# 5-1_fgpa_power.net
KiCad netlist of a schematic drawn in Altium Designer
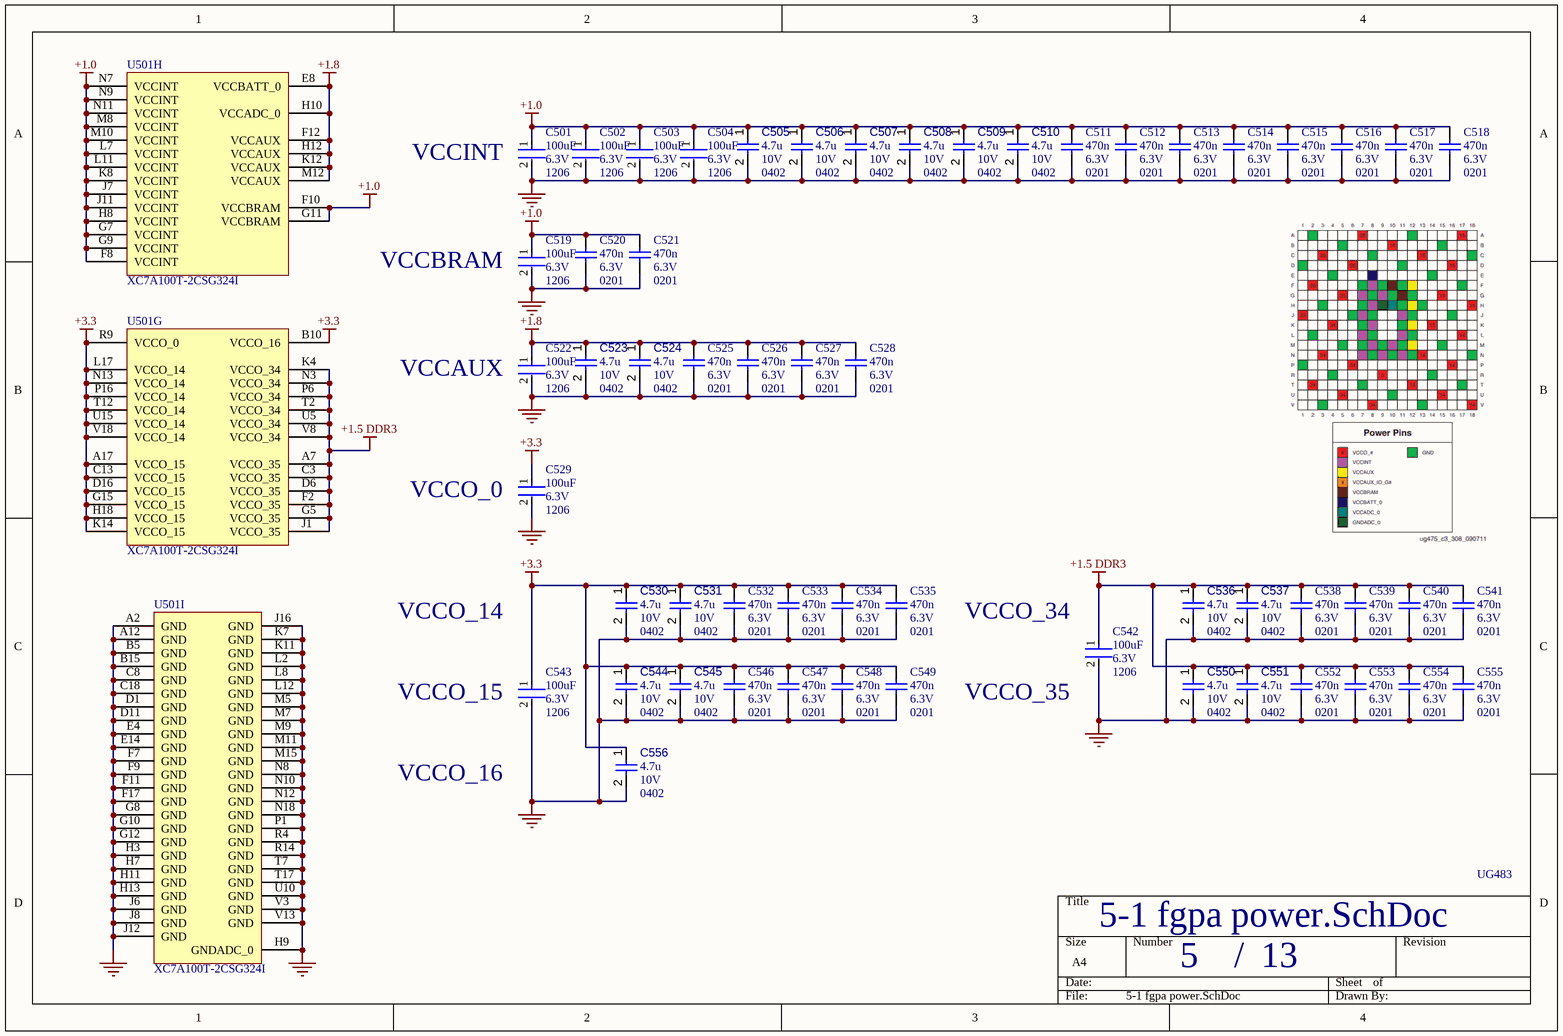
[diagram p0: 5-1 fgpa power.SchDoc]

(export (version "E")
  (design (tool "Eeschema 10.0.6"))
  (components
    (comp (ref "C501")
      (value "C1206C107M9PACTU")
      (footprint "FP-C1206C-EH-MFG")
      (description "CAP CER 100UF 6.3V X5R 1206")
      (fields
        (field (name "CASE CODE (IMPERIAL)") "1206")
        (field (name "VOLTAGE RATING (DC)") "6.3V")
        (field (name "TOLERANCE") "2%")
        (field (name "CAPACITANCE") "100uF")
        (field (name "VOLTAGE") "6.3V")
      )
      (libsource (lib "Altium Content Vault") (part "02cd4be3c70576c341d710602a673aa"))
    )
    (comp (ref "C502")
      (value "C1206C107M9PACTU")
      (footprint "FP-C1206C-EH-MFG")
      (description "CAP CER 100UF 6.3V X5R 1206")
      (fields
        (field (name "CASE CODE (IMPERIAL)") "1206")
        (field (name "VOLTAGE RATING (DC)") "6.3V")
        (field (name "TOLERANCE") "2%")
        (field (name "CAPACITANCE") "100uF")
        (field (name "VOLTAGE") "6.3V")
      )
      (libsource (lib "Altium Content Vault") (part "02cd4be3c70576c341d710602a673aa"))
    )
    (comp (ref "C503")
      (value "C1206C107M9PACTU")
      (footprint "FP-C1206C-EH-MFG")
      (description "CAP CER 100UF 6.3V X5R 1206")
      (fields
        (field (name "CASE CODE (IMPERIAL)") "1206")
        (field (name "VOLTAGE RATING (DC)") "6.3V")
        (field (name "TOLERANCE") "2%")
        (field (name "CAPACITANCE") "100uF")
        (field (name "VOLTAGE") "6.3V")
      )
      (libsource (lib "Altium Content Vault") (part "02cd4be3c70576c341d710602a673aa"))
    )
    (comp (ref "C504")
      (value "C1206C107M9PACTU")
      (footprint "FP-C1206C-EH-MFG")
      (description "CAP CER 100UF 6.3V X5R 1206")
      (fields
        (field (name "CASE CODE (IMPERIAL)") "1206")
        (field (name "VOLTAGE RATING (DC)") "6.3V")
        (field (name "TOLERANCE") "2%")
        (field (name "CAPACITANCE") "100uF")
        (field (name "VOLTAGE") "6.3V")
      )
      (libsource (lib "Altium Content Vault") (part "02cd4be3c70576c341d710602a673aa"))
    )
    (comp (ref "C505")
      (value "4.7u")
      (footprint "CAPC0402(1005)60_L")
      (description "Capacitor")
      (fields
        (field (name "CASE/PACKAGE") "0402")
        (field (name "VOLTAGE RATING") "10V")
        (field (name "Comment") "Capacitors,0402,4.7u,10V")
      )
      (libsource (lib "UBC Uncrewed Aircraft Systems") (part "CAP-NP-2"))
    )
    (comp (ref "C506")
      (value "4.7u")
      (footprint "CAPC0402(1005)60_L")
      (description "Capacitor")
      (fields
        (field (name "CASE/PACKAGE") "0402")
        (field (name "VOLTAGE RATING") "10V")
        (field (name "Comment") "Capacitors,0402,4.7u,10V")
      )
      (libsource (lib "UBC Uncrewed Aircraft Systems") (part "CAP-NP-2"))
    )
    (comp (ref "C507")
      (value "4.7u")
      (footprint "CAPC0402(1005)60_L")
      (description "Capacitor")
      (fields
        (field (name "CASE/PACKAGE") "0402")
        (field (name "VOLTAGE RATING") "10V")
        (field (name "Comment") "Capacitors,0402,4.7u,10V")
      )
      (libsource (lib "UBC Uncrewed Aircraft Systems") (part "CAP-NP-2"))
    )
    (comp (ref "C508")
      (value "4.7u")
      (footprint "CAPC0402(1005)60_L")
      (description "Capacitor")
      (fields
        (field (name "CASE/PACKAGE") "0402")
        (field (name "VOLTAGE RATING") "10V")
        (field (name "Comment") "Capacitors,0402,4.7u,10V")
      )
      (libsource (lib "UBC Uncrewed Aircraft Systems") (part "CAP-NP-2"))
    )
    (comp (ref "C509")
      (value "4.7u")
      (footprint "CAPC0402(1005)60_L")
      (description "Capacitor")
      (fields
        (field (name "CASE/PACKAGE") "0402")
        (field (name "VOLTAGE RATING") "10V")
        (field (name "Comment") "Capacitors,0402,4.7u,10V")
      )
      (libsource (lib "UBC Uncrewed Aircraft Systems") (part "CAP-NP-2"))
    )
    (comp (ref "C510")
      (value "4.7u")
      (footprint "CAPC0402(1005)60_L")
      (description "Capacitor")
      (fields
        (field (name "CASE/PACKAGE") "0402")
        (field (name "VOLTAGE RATING") "10V")
        (field (name "Comment") "Capacitors,0402,4.7u,10V")
      )
      (libsource (lib "UBC Uncrewed Aircraft Systems") (part "CAP-NP-2"))
    )
    (comp (ref "C511")
      (value "470n")
      (footprint "CAPC0603X33X15LL03T05")
      (fields
        (field (name "MANUFACTURER") "AVX Interconnect / Elco")
        (field (name "PART NUMBER") "02016D474KAT2A")
        (field (name "VOLTAGE RATING") "6.3V")
        (field (name "PACKAGE") "0201")
      )
      (libsource (lib "Altium Content Vault") (part "CAP"))
    )
    (comp (ref "C512")
      (value "470n")
      (footprint "CAPC0603X33X15LL03T05")
      (fields
        (field (name "MANUFACTURER") "AVX Interconnect / Elco")
        (field (name "PART NUMBER") "02016D474KAT2A")
        (field (name "VOLTAGE RATING") "6.3V")
        (field (name "PACKAGE") "0201")
      )
      (libsource (lib "Altium Content Vault") (part "CAP"))
    )
    (comp (ref "C513")
      (value "470n")
      (footprint "CAPC0603X33X15LL03T05")
      (fields
        (field (name "MANUFACTURER") "AVX Interconnect / Elco")
        (field (name "PART NUMBER") "02016D474KAT2A")
        (field (name "VOLTAGE RATING") "6.3V")
        (field (name "PACKAGE") "0201")
      )
      (libsource (lib "Altium Content Vault") (part "CAP"))
    )
    (comp (ref "C514")
      (value "470n")
      (footprint "CAPC0603X33X15LL03T05")
      (fields
        (field (name "MANUFACTURER") "AVX Interconnect / Elco")
        (field (name "PART NUMBER") "02016D474KAT2A")
        (field (name "VOLTAGE RATING") "6.3V")
        (field (name "PACKAGE") "0201")
      )
      (libsource (lib "Altium Content Vault") (part "CAP"))
    )
    (comp (ref "C515")
      (value "470n")
      (footprint "CAPC0603X33X15LL03T05")
      (fields
        (field (name "MANUFACTURER") "AVX Interconnect / Elco")
        (field (name "PART NUMBER") "02016D474KAT2A")
        (field (name "VOLTAGE RATING") "6.3V")
        (field (name "PACKAGE") "0201")
      )
      (libsource (lib "Altium Content Vault") (part "CAP"))
    )
    (comp (ref "C516")
      (value "470n")
      (footprint "CAPC0603X33X15LL03T05")
      (fields
        (field (name "MANUFACTURER") "AVX Interconnect / Elco")
        (field (name "PART NUMBER") "02016D474KAT2A")
        (field (name "VOLTAGE RATING") "6.3V")
        (field (name "PACKAGE") "0201")
      )
      (libsource (lib "Altium Content Vault") (part "CAP"))
    )
    (comp (ref "C517")
      (value "470n")
      (footprint "CAPC0603X33X15LL03T05")
      (fields
        (field (name "MANUFACTURER") "AVX Interconnect / Elco")
        (field (name "PART NUMBER") "02016D474KAT2A")
        (field (name "VOLTAGE RATING") "6.3V")
        (field (name "PACKAGE") "0201")
      )
      (libsource (lib "Altium Content Vault") (part "CAP"))
    )
    (comp (ref "C518")
      (value "470n")
      (footprint "CAPC0603X33X15LL03T05")
      (fields
        (field (name "MANUFACTURER") "AVX Interconnect / Elco")
        (field (name "PART NUMBER") "02016D474KAT2A")
        (field (name "VOLTAGE RATING") "6.3V")
        (field (name "PACKAGE") "0201")
      )
      (libsource (lib "Altium Content Vault") (part "CAP"))
    )
    (comp (ref "C519")
      (value "C1206C107M9PACTU")
      (footprint "FP-C1206C-EH-MFG")
      (description "CAP CER 100UF 6.3V X5R 1206")
      (fields
        (field (name "CASE CODE (IMPERIAL)") "1206")
        (field (name "VOLTAGE RATING (DC)") "6.3V")
        (field (name "TOLERANCE") "2%")
        (field (name "CAPACITANCE") "100uF")
        (field (name "VOLTAGE") "6.3V")
      )
      (libsource (lib "Altium Content Vault") (part "02cd4be3c70576c341d710602a673aa"))
    )
    (comp (ref "C520")
      (value "470n")
      (footprint "CAPC0603X33X15LL03T05")
      (fields
        (field (name "MANUFACTURER") "AVX Interconnect / Elco")
        (field (name "PART NUMBER") "02016D474KAT2A")
        (field (name "VOLTAGE RATING") "6.3V")
        (field (name "PACKAGE") "0201")
      )
      (libsource (lib "Altium Content Vault") (part "CAP"))
    )
    (comp (ref "C521")
      (value "470n")
      (footprint "CAPC0603X33X15LL03T05")
      (fields
        (field (name "MANUFACTURER") "AVX Interconnect / Elco")
        (field (name "PART NUMBER") "02016D474KAT2A")
        (field (name "VOLTAGE RATING") "6.3V")
        (field (name "PACKAGE") "0201")
      )
      (libsource (lib "Altium Content Vault") (part "CAP"))
    )
    (comp (ref "C522")
      (value "C1206C107M9PACTU")
      (footprint "FP-C1206C-EH-MFG")
      (description "CAP CER 100UF 6.3V X5R 1206")
      (fields
        (field (name "CASE CODE (IMPERIAL)") "1206")
        (field (name "VOLTAGE RATING (DC)") "6.3V")
        (field (name "TOLERANCE") "2%")
        (field (name "CAPACITANCE") "100uF")
        (field (name "VOLTAGE") "6.3V")
      )
      (libsource (lib "Altium Content Vault") (part "02cd4be3c70576c341d710602a673aa"))
    )
    (comp (ref "C523")
      (value "4.7u")
      (footprint "CAPC0402(1005)60_L")
      (description "Capacitor")
      (fields
        (field (name "CASE/PACKAGE") "0402")
        (field (name "VOLTAGE RATING") "10V")
        (field (name "Comment") "Capacitors,0402,4.7u,10V")
      )
      (libsource (lib "UBC Uncrewed Aircraft Systems") (part "CAP-NP-2"))
    )
    (comp (ref "C524")
      (value "4.7u")
      (footprint "CAPC0402(1005)60_L")
      (description "Capacitor")
      (fields
        (field (name "CASE/PACKAGE") "0402")
        (field (name "VOLTAGE RATING") "10V")
        (field (name "Comment") "Capacitors,0402,4.7u,10V")
      )
      (libsource (lib "UBC Uncrewed Aircraft Systems") (part "CAP-NP-2"))
    )
    (comp (ref "C525")
      (value "470n")
      (footprint "CAPC0603X33X15LL03T05")
      (fields
        (field (name "MANUFACTURER") "AVX Interconnect / Elco")
        (field (name "PART NUMBER") "02016D474KAT2A")
        (field (name "VOLTAGE RATING") "6.3V")
        (field (name "PACKAGE") "0201")
      )
      (libsource (lib "Altium Content Vault") (part "CAP"))
    )
    (comp (ref "C526")
      (value "470n")
      (footprint "CAPC0603X33X15LL03T05")
      (fields
        (field (name "MANUFACTURER") "AVX Interconnect / Elco")
        (field (name "PART NUMBER") "02016D474KAT2A")
        (field (name "VOLTAGE RATING") "6.3V")
        (field (name "PACKAGE") "0201")
      )
      (libsource (lib "Altium Content Vault") (part "CAP"))
    )
    (comp (ref "C527")
      (value "470n")
      (footprint "CAPC0603X33X15LL03T05")
      (fields
        (field (name "MANUFACTURER") "AVX Interconnect / Elco")
        (field (name "PART NUMBER") "02016D474KAT2A")
        (field (name "VOLTAGE RATING") "6.3V")
        (field (name "PACKAGE") "0201")
      )
      (libsource (lib "Altium Content Vault") (part "CAP"))
    )
    (comp (ref "C528")
      (value "470n")
      (footprint "CAPC0603X33X15LL03T05")
      (fields
        (field (name "MANUFACTURER") "AVX Interconnect / Elco")
        (field (name "PART NUMBER") "02016D474KAT2A")
        (field (name "VOLTAGE RATING") "6.3V")
        (field (name "PACKAGE") "0201")
      )
      (libsource (lib "Altium Content Vault") (part "CAP"))
    )
    (comp (ref "C529")
      (value "C1206C107M9PACTU")
      (footprint "FP-C1206C-EH-MFG")
      (description "CAP CER 100UF 6.3V X5R 1206")
      (fields
        (field (name "CASE CODE (IMPERIAL)") "1206")
        (field (name "VOLTAGE RATING (DC)") "6.3V")
        (field (name "TOLERANCE") "2%")
        (field (name "CAPACITANCE") "100uF")
        (field (name "VOLTAGE") "6.3V")
      )
      (libsource (lib "Altium Content Vault") (part "02cd4be3c70576c341d710602a673aa"))
    )
    (comp (ref "C530")
      (value "4.7u")
      (footprint "CAPC0402(1005)60_L")
      (description "Capacitor")
      (fields
        (field (name "CASE/PACKAGE") "0402")
        (field (name "VOLTAGE RATING") "10V")
        (field (name "Comment") "Capacitors,0402,4.7u,10V")
      )
      (libsource (lib "UBC Uncrewed Aircraft Systems") (part "CAP-NP-2"))
    )
    (comp (ref "C531")
      (value "4.7u")
      (footprint "CAPC0402(1005)60_L")
      (description "Capacitor")
      (fields
        (field (name "CASE/PACKAGE") "0402")
        (field (name "VOLTAGE RATING") "10V")
        (field (name "Comment") "Capacitors,0402,4.7u,10V")
      )
      (libsource (lib "UBC Uncrewed Aircraft Systems") (part "CAP-NP-2"))
    )
    (comp (ref "C532")
      (value "470n")
      (footprint "CAPC0603X33X15LL03T05")
      (fields
        (field (name "MANUFACTURER") "AVX Interconnect / Elco")
        (field (name "PART NUMBER") "02016D474KAT2A")
        (field (name "VOLTAGE RATING") "6.3V")
        (field (name "PACKAGE") "0201")
      )
      (libsource (lib "Altium Content Vault") (part "CAP"))
    )
    (comp (ref "C533")
      (value "470n")
      (footprint "CAPC0603X33X15LL03T05")
      (fields
        (field (name "MANUFACTURER") "AVX Interconnect / Elco")
        (field (name "PART NUMBER") "02016D474KAT2A")
        (field (name "VOLTAGE RATING") "6.3V")
        (field (name "PACKAGE") "0201")
      )
      (libsource (lib "Altium Content Vault") (part "CAP"))
    )
    (comp (ref "C534")
      (value "470n")
      (footprint "CAPC0603X33X15LL03T05")
      (fields
        (field (name "MANUFACTURER") "AVX Interconnect / Elco")
        (field (name "PART NUMBER") "02016D474KAT2A")
        (field (name "VOLTAGE RATING") "6.3V")
        (field (name "PACKAGE") "0201")
      )
      (libsource (lib "Altium Content Vault") (part "CAP"))
    )
    (comp (ref "C535")
      (value "470n")
      (footprint "CAPC0603X33X15LL03T05")
      (fields
        (field (name "MANUFACTURER") "AVX Interconnect / Elco")
        (field (name "PART NUMBER") "02016D474KAT2A")
        (field (name "VOLTAGE RATING") "6.3V")
        (field (name "PACKAGE") "0201")
      )
      (libsource (lib "Altium Content Vault") (part "CAP"))
    )
    (comp (ref "C536")
      (value "4.7u")
      (footprint "CAPC0402(1005)60_L")
      (description "Capacitor")
      (fields
        (field (name "CASE/PACKAGE") "0402")
        (field (name "VOLTAGE RATING") "10V")
        (field (name "Comment") "Capacitors,0402,4.7u,10V")
      )
      (libsource (lib "UBC Uncrewed Aircraft Systems") (part "CAP-NP-2"))
    )
    (comp (ref "C537")
      (value "4.7u")
      (footprint "CAPC0402(1005)60_L")
      (description "Capacitor")
      (fields
        (field (name "CASE/PACKAGE") "0402")
        (field (name "VOLTAGE RATING") "10V")
        (field (name "Comment") "Capacitors,0402,4.7u,10V")
      )
      (libsource (lib "UBC Uncrewed Aircraft Systems") (part "CAP-NP-2"))
    )
    (comp (ref "C538")
      (value "470n")
      (footprint "CAPC0603X33X15LL03T05")
      (fields
        (field (name "MANUFACTURER") "AVX Interconnect / Elco")
        (field (name "PART NUMBER") "02016D474KAT2A")
        (field (name "VOLTAGE RATING") "6.3V")
        (field (name "PACKAGE") "0201")
      )
      (libsource (lib "Altium Content Vault") (part "CAP"))
    )
    (comp (ref "C539")
      (value "470n")
      (footprint "CAPC0603X33X15LL03T05")
      (fields
        (field (name "MANUFACTURER") "AVX Interconnect / Elco")
        (field (name "PART NUMBER") "02016D474KAT2A")
        (field (name "VOLTAGE RATING") "6.3V")
        (field (name "PACKAGE") "0201")
      )
      (libsource (lib "Altium Content Vault") (part "CAP"))
    )
    (comp (ref "C540")
      (value "470n")
      (footprint "CAPC0603X33X15LL03T05")
      (fields
        (field (name "MANUFACTURER") "AVX Interconnect / Elco")
        (field (name "PART NUMBER") "02016D474KAT2A")
        (field (name "VOLTAGE RATING") "6.3V")
        (field (name "PACKAGE") "0201")
      )
      (libsource (lib "Altium Content Vault") (part "CAP"))
    )
    (comp (ref "C541")
      (value "470n")
      (footprint "CAPC0603X33X15LL03T05")
      (fields
        (field (name "MANUFACTURER") "AVX Interconnect / Elco")
        (field (name "PART NUMBER") "02016D474KAT2A")
        (field (name "VOLTAGE RATING") "6.3V")
        (field (name "PACKAGE") "0201")
      )
      (libsource (lib "Altium Content Vault") (part "CAP"))
    )
    (comp (ref "C542")
      (value "C1206C107M9PACTU")
      (footprint "FP-C1206C-EH-MFG")
      (description "CAP CER 100UF 6.3V X5R 1206")
      (fields
        (field (name "CASE CODE (IMPERIAL)") "1206")
        (field (name "VOLTAGE RATING (DC)") "6.3V")
        (field (name "TOLERANCE") "2%")
        (field (name "CAPACITANCE") "100uF")
        (field (name "VOLTAGE") "6.3V")
      )
      (libsource (lib "Altium Content Vault") (part "02cd4be3c70576c341d710602a673aa"))
    )
    (comp (ref "C543")
      (value "C1206C107M9PACTU")
      (footprint "FP-C1206C-EH-MFG")
      (description "CAP CER 100UF 6.3V X5R 1206")
      (fields
        (field (name "CASE CODE (IMPERIAL)") "1206")
        (field (name "VOLTAGE RATING (DC)") "6.3V")
        (field (name "TOLERANCE") "2%")
        (field (name "CAPACITANCE") "100uF")
        (field (name "VOLTAGE") "6.3V")
      )
      (libsource (lib "Altium Content Vault") (part "02cd4be3c70576c341d710602a673aa"))
    )
    (comp (ref "C544")
      (value "4.7u")
      (footprint "CAPC0402(1005)60_L")
      (description "Capacitor")
      (fields
        (field (name "CASE/PACKAGE") "0402")
        (field (name "VOLTAGE RATING") "10V")
        (field (name "Comment") "Capacitors,0402,4.7u,10V")
      )
      (libsource (lib "UBC Uncrewed Aircraft Systems") (part "CAP-NP-2"))
    )
    (comp (ref "C545")
      (value "4.7u")
      (footprint "CAPC0402(1005)60_L")
      (description "Capacitor")
      (fields
        (field (name "CASE/PACKAGE") "0402")
        (field (name "VOLTAGE RATING") "10V")
        (field (name "Comment") "Capacitors,0402,4.7u,10V")
      )
      (libsource (lib "UBC Uncrewed Aircraft Systems") (part "CAP-NP-2"))
    )
    (comp (ref "C546")
      (value "470n")
      (footprint "CAPC0603X33X15LL03T05")
      (fields
        (field (name "MANUFACTURER") "AVX Interconnect / Elco")
        (field (name "PART NUMBER") "02016D474KAT2A")
        (field (name "VOLTAGE RATING") "6.3V")
        (field (name "PACKAGE") "0201")
      )
      (libsource (lib "Altium Content Vault") (part "CAP"))
    )
    (comp (ref "C547")
      (value "470n")
      (footprint "CAPC0603X33X15LL03T05")
      (fields
        (field (name "MANUFACTURER") "AVX Interconnect / Elco")
        (field (name "PART NUMBER") "02016D474KAT2A")
        (field (name "VOLTAGE RATING") "6.3V")
        (field (name "PACKAGE") "0201")
      )
      (libsource (lib "Altium Content Vault") (part "CAP"))
    )
    (comp (ref "C548")
      (value "470n")
      (footprint "CAPC0603X33X15LL03T05")
      (fields
        (field (name "MANUFACTURER") "AVX Interconnect / Elco")
        (field (name "PART NUMBER") "02016D474KAT2A")
        (field (name "VOLTAGE RATING") "6.3V")
        (field (name "PACKAGE") "0201")
      )
      (libsource (lib "Altium Content Vault") (part "CAP"))
    )
    (comp (ref "C549")
      (value "470n")
      (footprint "CAPC0603X33X15LL03T05")
      (fields
        (field (name "MANUFACTURER") "AVX Interconnect / Elco")
        (field (name "PART NUMBER") "02016D474KAT2A")
        (field (name "VOLTAGE RATING") "6.3V")
        (field (name "PACKAGE") "0201")
      )
      (libsource (lib "Altium Content Vault") (part "CAP"))
    )
    (comp (ref "C550")
      (value "4.7u")
      (footprint "CAPC0402(1005)60_L")
      (description "Capacitor")
      (fields
        (field (name "CASE/PACKAGE") "0402")
        (field (name "VOLTAGE RATING") "10V")
        (field (name "Comment") "Capacitors,0402,4.7u,10V")
      )
      (libsource (lib "UBC Uncrewed Aircraft Systems") (part "CAP-NP-2"))
    )
    (comp (ref "C551")
      (value "4.7u")
      (footprint "CAPC0402(1005)60_L")
      (description "Capacitor")
      (fields
        (field (name "CASE/PACKAGE") "0402")
        (field (name "VOLTAGE RATING") "10V")
        (field (name "Comment") "Capacitors,0402,4.7u,10V")
      )
      (libsource (lib "UBC Uncrewed Aircraft Systems") (part "CAP-NP-2"))
    )
    (comp (ref "C552")
      (value "470n")
      (footprint "CAPC0603X33X15LL03T05")
      (fields
        (field (name "MANUFACTURER") "AVX Interconnect / Elco")
        (field (name "PART NUMBER") "02016D474KAT2A")
        (field (name "VOLTAGE RATING") "6.3V")
        (field (name "PACKAGE") "0201")
      )
      (libsource (lib "Altium Content Vault") (part "CAP"))
    )
    (comp (ref "C553")
      (value "470n")
      (footprint "CAPC0603X33X15LL03T05")
      (fields
        (field (name "MANUFACTURER") "AVX Interconnect / Elco")
        (field (name "PART NUMBER") "02016D474KAT2A")
        (field (name "VOLTAGE RATING") "6.3V")
        (field (name "PACKAGE") "0201")
      )
      (libsource (lib "Altium Content Vault") (part "CAP"))
    )
    (comp (ref "C554")
      (value "470n")
      (footprint "CAPC0603X33X15LL03T05")
      (fields
        (field (name "MANUFACTURER") "AVX Interconnect / Elco")
        (field (name "PART NUMBER") "02016D474KAT2A")
        (field (name "VOLTAGE RATING") "6.3V")
        (field (name "PACKAGE") "0201")
      )
      (libsource (lib "Altium Content Vault") (part "CAP"))
    )
    (comp (ref "C555")
      (value "470n")
      (footprint "CAPC0603X33X15LL03T05")
      (fields
        (field (name "MANUFACTURER") "AVX Interconnect / Elco")
        (field (name "PART NUMBER") "02016D474KAT2A")
        (field (name "VOLTAGE RATING") "6.3V")
        (field (name "PACKAGE") "0201")
      )
      (libsource (lib "Altium Content Vault") (part "CAP"))
    )
    (comp (ref "C556")
      (value "4.7u")
      (footprint "CAPC0402(1005)60_L")
      (description "Capacitor")
      (fields
        (field (name "CASE/PACKAGE") "0402")
        (field (name "VOLTAGE RATING") "10V")
        (field (name "Comment") "Capacitors,0402,4.7u,10V")
      )
      (libsource (lib "UBC Uncrewed Aircraft Systems") (part "CAP-NP-2"))
    )
    (comp (ref "U501")
      (value "XC7A100T-2CSG324I")
      (footprint "CSG324")
      (description "Artix-7 FPGA, 210 User I/Os, 0 GTP, 324-Ball BGA, Speed Grade 2, Extended Grade, Pb-Free")
      (fields (field (name "MANUFACTURER") "Xilinx") (field (name "GENERIC PART NUMBER") "XC7A100T"))
      (libsource (lib "Altium Content Vault") (part "XNLX-XC7A100T-XNLX-CSG324"))
    )
  )
  (nets
    (net (code "1") (name "+1.0") (class "Default")
      (node (ref "C501") (pin "1") (pinfunction "1_1") (pintype "passive"))
      (node (ref "C502") (pin "1") (pinfunction "1_1") (pintype "passive"))
      (node (ref "C503") (pin "1") (pinfunction "1_1") (pintype "passive"))
      (node (ref "C504") (pin "1") (pinfunction "1_1") (pintype "passive"))
      (node (ref "C505") (pin "1") (pinfunction "1_1") (pintype "passive"))
      (node (ref "C506") (pin "1") (pinfunction "1_1") (pintype "passive"))
      (node (ref "C507") (pin "1") (pinfunction "1_1") (pintype "passive"))
      (node (ref "C508") (pin "1") (pinfunction "1_1") (pintype "passive"))
      (node (ref "C509") (pin "1") (pinfunction "1_1") (pintype "passive"))
      (node (ref "C510") (pin "1") (pinfunction "1_1") (pintype "passive"))
      (node (ref "C511") (pin "1") (pinfunction "1_1") (pintype "passive"))
      (node (ref "C512") (pin "1") (pinfunction "1_1") (pintype "passive"))
      (node (ref "C513") (pin "1") (pinfunction "1_1") (pintype "passive"))
      (node (ref "C514") (pin "1") (pinfunction "1_1") (pintype "passive"))
      (node (ref "C515") (pin "1") (pinfunction "1_1") (pintype "passive"))
      (node (ref "C516") (pin "1") (pinfunction "1_1") (pintype "passive"))
      (node (ref "C517") (pin "1") (pinfunction "1_1") (pintype "passive"))
      (node (ref "C518") (pin "1") (pinfunction "1_1") (pintype "passive"))
      (node (ref "C519") (pin "1") (pinfunction "1_1") (pintype "passive"))
      (node (ref "C520") (pin "1") (pinfunction "1_1") (pintype "passive"))
      (node (ref "C521") (pin "1") (pinfunction "1_1") (pintype "passive"))
      (node (ref "U501") (pin "F10") (pinfunction "VCCBRAM_F10") (pintype "power_in"))
      (node (ref "U501") (pin "F8") (pinfunction "VCCINT_F8") (pintype "power_in"))
      (node (ref "U501") (pin "G11") (pinfunction "VCCBRAM_G11") (pintype "power_in"))
      (node (ref "U501") (pin "G7") (pinfunction "VCCINT_G7") (pintype "power_in"))
      (node (ref "U501") (pin "G9") (pinfunction "VCCINT_G9") (pintype "power_in"))
      (node (ref "U501") (pin "H8") (pinfunction "VCCINT_H8") (pintype "power_in"))
      (node (ref "U501") (pin "J11") (pinfunction "VCCINT_J11") (pintype "power_in"))
      (node (ref "U501") (pin "J7") (pinfunction "VCCINT_J7") (pintype "power_in"))
      (node (ref "U501") (pin "K8") (pinfunction "VCCINT_K8") (pintype "power_in"))
      (node (ref "U501") (pin "L11") (pinfunction "VCCINT_L11") (pintype "power_in"))
      (node (ref "U501") (pin "L7") (pinfunction "VCCINT_L7") (pintype "power_in"))
      (node (ref "U501") (pin "M10") (pinfunction "VCCINT_M10") (pintype "power_in"))
      (node (ref "U501") (pin "M8") (pinfunction "VCCINT_M8") (pintype "power_in"))
      (node (ref "U501") (pin "N11") (pinfunction "VCCINT_N11") (pintype "power_in"))
      (node (ref "U501") (pin "N7") (pinfunction "VCCINT_N7") (pintype "power_in"))
      (node (ref "U501") (pin "N9") (pinfunction "VCCINT_N9") (pintype "power_in"))
    )
    (net (code "2") (name "+1.5 DDR3") (class "Default")
      (node (ref "C536") (pin "1") (pinfunction "1_1") (pintype "passive"))
      (node (ref "C537") (pin "1") (pinfunction "1_1") (pintype "passive"))
      (node (ref "C538") (pin "1") (pinfunction "1_1") (pintype "passive"))
      (node (ref "C539") (pin "1") (pinfunction "1_1") (pintype "passive"))
      (node (ref "C540") (pin "1") (pinfunction "1_1") (pintype "passive"))
      (node (ref "C541") (pin "1") (pinfunction "1_1") (pintype "passive"))
      (node (ref "C542") (pin "1") (pinfunction "1_1") (pintype "passive"))
      (node (ref "C550") (pin "1") (pinfunction "1_1") (pintype "passive"))
      (node (ref "C551") (pin "1") (pinfunction "1_1") (pintype "passive"))
      (node (ref "C552") (pin "1") (pinfunction "1_1") (pintype "passive"))
      (node (ref "C553") (pin "1") (pinfunction "1_1") (pintype "passive"))
      (node (ref "C554") (pin "1") (pinfunction "1_1") (pintype "passive"))
      (node (ref "C555") (pin "1") (pinfunction "1_1") (pintype "passive"))
      (node (ref "U501") (pin "A7") (pinfunction "VCCO_35_A7") (pintype "power_in"))
      (node (ref "U501") (pin "C3") (pinfunction "VCCO_35_C3") (pintype "power_in"))
      (node (ref "U501") (pin "D6") (pinfunction "VCCO_35_D6") (pintype "power_in"))
      (node (ref "U501") (pin "F2") (pinfunction "VCCO_35_F2") (pintype "power_in"))
      (node (ref "U501") (pin "G5") (pinfunction "VCCO_35_G5") (pintype "power_in"))
      (node (ref "U501") (pin "J1") (pinfunction "VCCO_35_J1") (pintype "power_in"))
      (node (ref "U501") (pin "K4") (pinfunction "VCCO_34_K4") (pintype "power_in"))
      (node (ref "U501") (pin "N3") (pinfunction "VCCO_34_N3") (pintype "power_in"))
      (node (ref "U501") (pin "P6") (pinfunction "VCCO_34_P6") (pintype "power_in"))
      (node (ref "U501") (pin "T2") (pinfunction "VCCO_34_T2") (pintype "power_in"))
      (node (ref "U501") (pin "U5") (pinfunction "VCCO_34_U5") (pintype "power_in"))
      (node (ref "U501") (pin "V8") (pinfunction "VCCO_34_V8") (pintype "power_in"))
    )
    (net (code "3") (name "+1.8") (class "Default")
      (node (ref "C522") (pin "1") (pinfunction "1_1") (pintype "passive"))
      (node (ref "C523") (pin "1") (pinfunction "1_1") (pintype "passive"))
      (node (ref "C524") (pin "1") (pinfunction "1_1") (pintype "passive"))
      (node (ref "C525") (pin "1") (pinfunction "1_1") (pintype "passive"))
      (node (ref "C526") (pin "1") (pinfunction "1_1") (pintype "passive"))
      (node (ref "C527") (pin "1") (pinfunction "1_1") (pintype "passive"))
      (node (ref "C528") (pin "1") (pinfunction "1_1") (pintype "passive"))
      (node (ref "U501") (pin "E8") (pinfunction "VCCBATT_0_E8") (pintype "power_in"))
      (node (ref "U501") (pin "F12") (pinfunction "VCCAUX_F12") (pintype "power_in"))
      (node (ref "U501") (pin "H10") (pinfunction "VCCADC_0_H10") (pintype "power_in"))
      (node (ref "U501") (pin "H12") (pinfunction "VCCAUX_H12") (pintype "power_in"))
      (node (ref "U501") (pin "K12") (pinfunction "VCCAUX_K12") (pintype "power_in"))
      (node (ref "U501") (pin "M12") (pinfunction "VCCAUX_M12") (pintype "power_in"))
    )
    (net (code "4") (name "+3.3") (class "Default")
      (node (ref "C529") (pin "1") (pinfunction "1_1") (pintype "passive"))
      (node (ref "C530") (pin "1") (pinfunction "1_1") (pintype "passive"))
      (node (ref "C531") (pin "1") (pinfunction "1_1") (pintype "passive"))
      (node (ref "C532") (pin "1") (pinfunction "1_1") (pintype "passive"))
      (node (ref "C533") (pin "1") (pinfunction "1_1") (pintype "passive"))
      (node (ref "C534") (pin "1") (pinfunction "1_1") (pintype "passive"))
      (node (ref "C535") (pin "1") (pinfunction "1_1") (pintype "passive"))
      (node (ref "C543") (pin "1") (pinfunction "1_1") (pintype "passive"))
      (node (ref "C544") (pin "1") (pinfunction "1_1") (pintype "passive"))
      (node (ref "C545") (pin "1") (pinfunction "1_1") (pintype "passive"))
      (node (ref "C546") (pin "1") (pinfunction "1_1") (pintype "passive"))
      (node (ref "C547") (pin "1") (pinfunction "1_1") (pintype "passive"))
      (node (ref "C548") (pin "1") (pinfunction "1_1") (pintype "passive"))
      (node (ref "C549") (pin "1") (pinfunction "1_1") (pintype "passive"))
      (node (ref "C556") (pin "1") (pinfunction "1_1") (pintype "passive"))
      (node (ref "U501") (pin "A17") (pinfunction "VCCO_15_A17") (pintype "power_in"))
      (node (ref "U501") (pin "B10") (pinfunction "VCCO_16_B10") (pintype "power_in"))
      (node (ref "U501") (pin "C13") (pinfunction "VCCO_15_C13") (pintype "power_in"))
      (node (ref "U501") (pin "D16") (pinfunction "VCCO_15_D16") (pintype "power_in"))
      (node (ref "U501") (pin "G15") (pinfunction "VCCO_15_G15") (pintype "power_in"))
      (node (ref "U501") (pin "H18") (pinfunction "VCCO_15_H18") (pintype "power_in"))
      (node (ref "U501") (pin "K14") (pinfunction "VCCO_15_K14") (pintype "power_in"))
      (node (ref "U501") (pin "L17") (pinfunction "VCCO_14_L17") (pintype "power_in"))
      (node (ref "U501") (pin "N13") (pinfunction "VCCO_14_N13") (pintype "power_in"))
      (node (ref "U501") (pin "P16") (pinfunction "VCCO_14_P16") (pintype "power_in"))
      (node (ref "U501") (pin "R9") (pinfunction "VCCO_0_R9") (pintype "power_in"))
      (node (ref "U501") (pin "T12") (pinfunction "VCCO_14_T12") (pintype "power_in"))
      (node (ref "U501") (pin "U15") (pinfunction "VCCO_14_U15") (pintype "power_in"))
      (node (ref "U501") (pin "V18") (pinfunction "VCCO_14_V18") (pintype "power_in"))
    )
    (net (code "5") (name "GND") (class "Default")
      (node (ref "C501") (pin "2") (pinfunction "2_2") (pintype "passive"))
      (node (ref "C502") (pin "2") (pinfunction "2_2") (pintype "passive"))
      (node (ref "C503") (pin "2") (pinfunction "2_2") (pintype "passive"))
      (node (ref "C504") (pin "2") (pinfunction "2_2") (pintype "passive"))
      (node (ref "C505") (pin "2") (pinfunction "2_2") (pintype "passive"))
      (node (ref "C506") (pin "2") (pinfunction "2_2") (pintype "passive"))
      (node (ref "C507") (pin "2") (pinfunction "2_2") (pintype "passive"))
      (node (ref "C508") (pin "2") (pinfunction "2_2") (pintype "passive"))
      (node (ref "C509") (pin "2") (pinfunction "2_2") (pintype "passive"))
      (node (ref "C510") (pin "2") (pinfunction "2_2") (pintype "passive"))
      (node (ref "C511") (pin "2") (pinfunction "2_2") (pintype "passive"))
      (node (ref "C512") (pin "2") (pinfunction "2_2") (pintype "passive"))
      (node (ref "C513") (pin "2") (pinfunction "2_2") (pintype "passive"))
      (node (ref "C514") (pin "2") (pinfunction "2_2") (pintype "passive"))
      (node (ref "C515") (pin "2") (pinfunction "2_2") (pintype "passive"))
      (node (ref "C516") (pin "2") (pinfunction "2_2") (pintype "passive"))
      (node (ref "C517") (pin "2") (pinfunction "2_2") (pintype "passive"))
      (node (ref "C518") (pin "2") (pinfunction "2_2") (pintype "passive"))
      (node (ref "C519") (pin "2") (pinfunction "2_2") (pintype "passive"))
      (node (ref "C520") (pin "2") (pinfunction "2_2") (pintype "passive"))
      (node (ref "C521") (pin "2") (pinfunction "2_2") (pintype "passive"))
      (node (ref "C522") (pin "2") (pinfunction "2_2") (pintype "passive"))
      (node (ref "C523") (pin "2") (pinfunction "2_2") (pintype "passive"))
      (node (ref "C524") (pin "2") (pinfunction "2_2") (pintype "passive"))
      (node (ref "C525") (pin "2") (pinfunction "2_2") (pintype "passive"))
      (node (ref "C526") (pin "2") (pinfunction "2_2") (pintype "passive"))
      (node (ref "C527") (pin "2") (pinfunction "2_2") (pintype "passive"))
      (node (ref "C528") (pin "2") (pinfunction "2_2") (pintype "passive"))
      (node (ref "C529") (pin "2") (pinfunction "2_2") (pintype "passive"))
      (node (ref "C530") (pin "2") (pinfunction "2_2") (pintype "passive"))
      (node (ref "C531") (pin "2") (pinfunction "2_2") (pintype "passive"))
      (node (ref "C532") (pin "2") (pinfunction "2_2") (pintype "passive"))
      (node (ref "C533") (pin "2") (pinfunction "2_2") (pintype "passive"))
      (node (ref "C534") (pin "2") (pinfunction "2_2") (pintype "passive"))
      (node (ref "C535") (pin "2") (pinfunction "2_2") (pintype "passive"))
      (node (ref "C536") (pin "2") (pinfunction "2_2") (pintype "passive"))
      (node (ref "C537") (pin "2") (pinfunction "2_2") (pintype "passive"))
      (node (ref "C538") (pin "2") (pinfunction "2_2") (pintype "passive"))
      (node (ref "C539") (pin "2") (pinfunction "2_2") (pintype "passive"))
      (node (ref "C540") (pin "2") (pinfunction "2_2") (pintype "passive"))
      (node (ref "C541") (pin "2") (pinfunction "2_2") (pintype "passive"))
      (node (ref "C542") (pin "2") (pinfunction "2_2") (pintype "passive"))
      (node (ref "C543") (pin "2") (pinfunction "2_2") (pintype "passive"))
      (node (ref "C544") (pin "2") (pinfunction "2_2") (pintype "passive"))
      (node (ref "C545") (pin "2") (pinfunction "2_2") (pintype "passive"))
      (node (ref "C546") (pin "2") (pinfunction "2_2") (pintype "passive"))
      (node (ref "C547") (pin "2") (pinfunction "2_2") (pintype "passive"))
      (node (ref "C548") (pin "2") (pinfunction "2_2") (pintype "passive"))
      (node (ref "C549") (pin "2") (pinfunction "2_2") (pintype "passive"))
      (node (ref "C550") (pin "2") (pinfunction "2_2") (pintype "passive"))
      (node (ref "C551") (pin "2") (pinfunction "2_2") (pintype "passive"))
      (node (ref "C552") (pin "2") (pinfunction "2_2") (pintype "passive"))
      (node (ref "C553") (pin "2") (pinfunction "2_2") (pintype "passive"))
      (node (ref "C554") (pin "2") (pinfunction "2_2") (pintype "passive"))
      (node (ref "C555") (pin "2") (pinfunction "2_2") (pintype "passive"))
      (node (ref "C556") (pin "2") (pinfunction "2_2") (pintype "passive"))
      (node (ref "U501") (pin "A12") (pinfunction "GND_A12") (pintype "power_in"))
      (node (ref "U501") (pin "A2") (pinfunction "GND_A2") (pintype "power_in"))
      (node (ref "U501") (pin "B15") (pinfunction "GND_B15") (pintype "power_in"))
      (node (ref "U501") (pin "B5") (pinfunction "GND_B5") (pintype "power_in"))
      (node (ref "U501") (pin "C18") (pinfunction "GND_C18") (pintype "power_in"))
      (node (ref "U501") (pin "C8") (pinfunction "GND_C8") (pintype "power_in"))
      (node (ref "U501") (pin "D1") (pinfunction "GND_D1") (pintype "power_in"))
      (node (ref "U501") (pin "D11") (pinfunction "GND_D11") (pintype "power_in"))
      (node (ref "U501") (pin "E14") (pinfunction "GND_E14") (pintype "power_in"))
      (node (ref "U501") (pin "E4") (pinfunction "GND_E4") (pintype "power_in"))
      (node (ref "U501") (pin "F11") (pinfunction "GND_F11") (pintype "power_in"))
      (node (ref "U501") (pin "F17") (pinfunction "GND_F17") (pintype "power_in"))
      (node (ref "U501") (pin "F7") (pinfunction "GND_F7") (pintype "power_in"))
      (node (ref "U501") (pin "F9") (pinfunction "GND_F9") (pintype "power_in"))
      (node (ref "U501") (pin "G10") (pinfunction "GND_G10") (pintype "power_in"))
      (node (ref "U501") (pin "G12") (pinfunction "GND_G12") (pintype "power_in"))
      (node (ref "U501") (pin "G8") (pinfunction "GND_G8") (pintype "power_in"))
      (node (ref "U501") (pin "H11") (pinfunction "GND_H11") (pintype "power_in"))
      (node (ref "U501") (pin "H13") (pinfunction "GND_H13") (pintype "power_in"))
      (node (ref "U501") (pin "H3") (pinfunction "GND_H3") (pintype "power_in"))
      (node (ref "U501") (pin "H7") (pinfunction "GND_H7") (pintype "power_in"))
      (node (ref "U501") (pin "H9") (pinfunction "GNDADC_0_H9") (pintype "power_in"))
      (node (ref "U501") (pin "J12") (pinfunction "GND_J12") (pintype "power_in"))
      (node (ref "U501") (pin "J16") (pinfunction "GND_J16") (pintype "power_in"))
      (node (ref "U501") (pin "J6") (pinfunction "GND_J6") (pintype "power_in"))
      (node (ref "U501") (pin "J8") (pinfunction "GND_J8") (pintype "power_in"))
      (node (ref "U501") (pin "K11") (pinfunction "GND_K11") (pintype "power_in"))
      (node (ref "U501") (pin "K7") (pinfunction "GND_K7") (pintype "power_in"))
      (node (ref "U501") (pin "L12") (pinfunction "GND_L12") (pintype "power_in"))
      (node (ref "U501") (pin "L2") (pinfunction "GND_L2") (pintype "power_in"))
      (node (ref "U501") (pin "L8") (pinfunction "GND_L8") (pintype "power_in"))
      (node (ref "U501") (pin "M11") (pinfunction "GND_M11") (pintype "power_in"))
      (node (ref "U501") (pin "M15") (pinfunction "GND_M15") (pintype "power_in"))
      (node (ref "U501") (pin "M5") (pinfunction "GND_M5") (pintype "power_in"))
      (node (ref "U501") (pin "M7") (pinfunction "GND_M7") (pintype "power_in"))
      (node (ref "U501") (pin "M9") (pinfunction "GND_M9") (pintype "power_in"))
      (node (ref "U501") (pin "N10") (pinfunction "GND_N10") (pintype "power_in"))
      (node (ref "U501") (pin "N12") (pinfunction "GND_N12") (pintype "power_in"))
      (node (ref "U501") (pin "N18") (pinfunction "GND_N18") (pintype "power_in"))
      (node (ref "U501") (pin "N8") (pinfunction "GND_N8") (pintype "power_in"))
      (node (ref "U501") (pin "P1") (pinfunction "GND_P1") (pintype "power_in"))
      (node (ref "U501") (pin "R14") (pinfunction "GND_R14") (pintype "power_in"))
      (node (ref "U501") (pin "R4") (pinfunction "GND_R4") (pintype "power_in"))
      (node (ref "U501") (pin "T17") (pinfunction "GND_T17") (pintype "power_in"))
      (node (ref "U501") (pin "T7") (pinfunction "GND_T7") (pintype "power_in"))
      (node (ref "U501") (pin "U10") (pinfunction "GND_U10") (pintype "power_in"))
      (node (ref "U501") (pin "V13") (pinfunction "GND_V13") (pintype "power_in"))
      (node (ref "U501") (pin "V3") (pinfunction "GND_V3") (pintype "power_in"))
    )
  )
)
